# LG_G6_controller_2021-01-08.net
KiCad netlist of a schematic drawn in EasyEDA
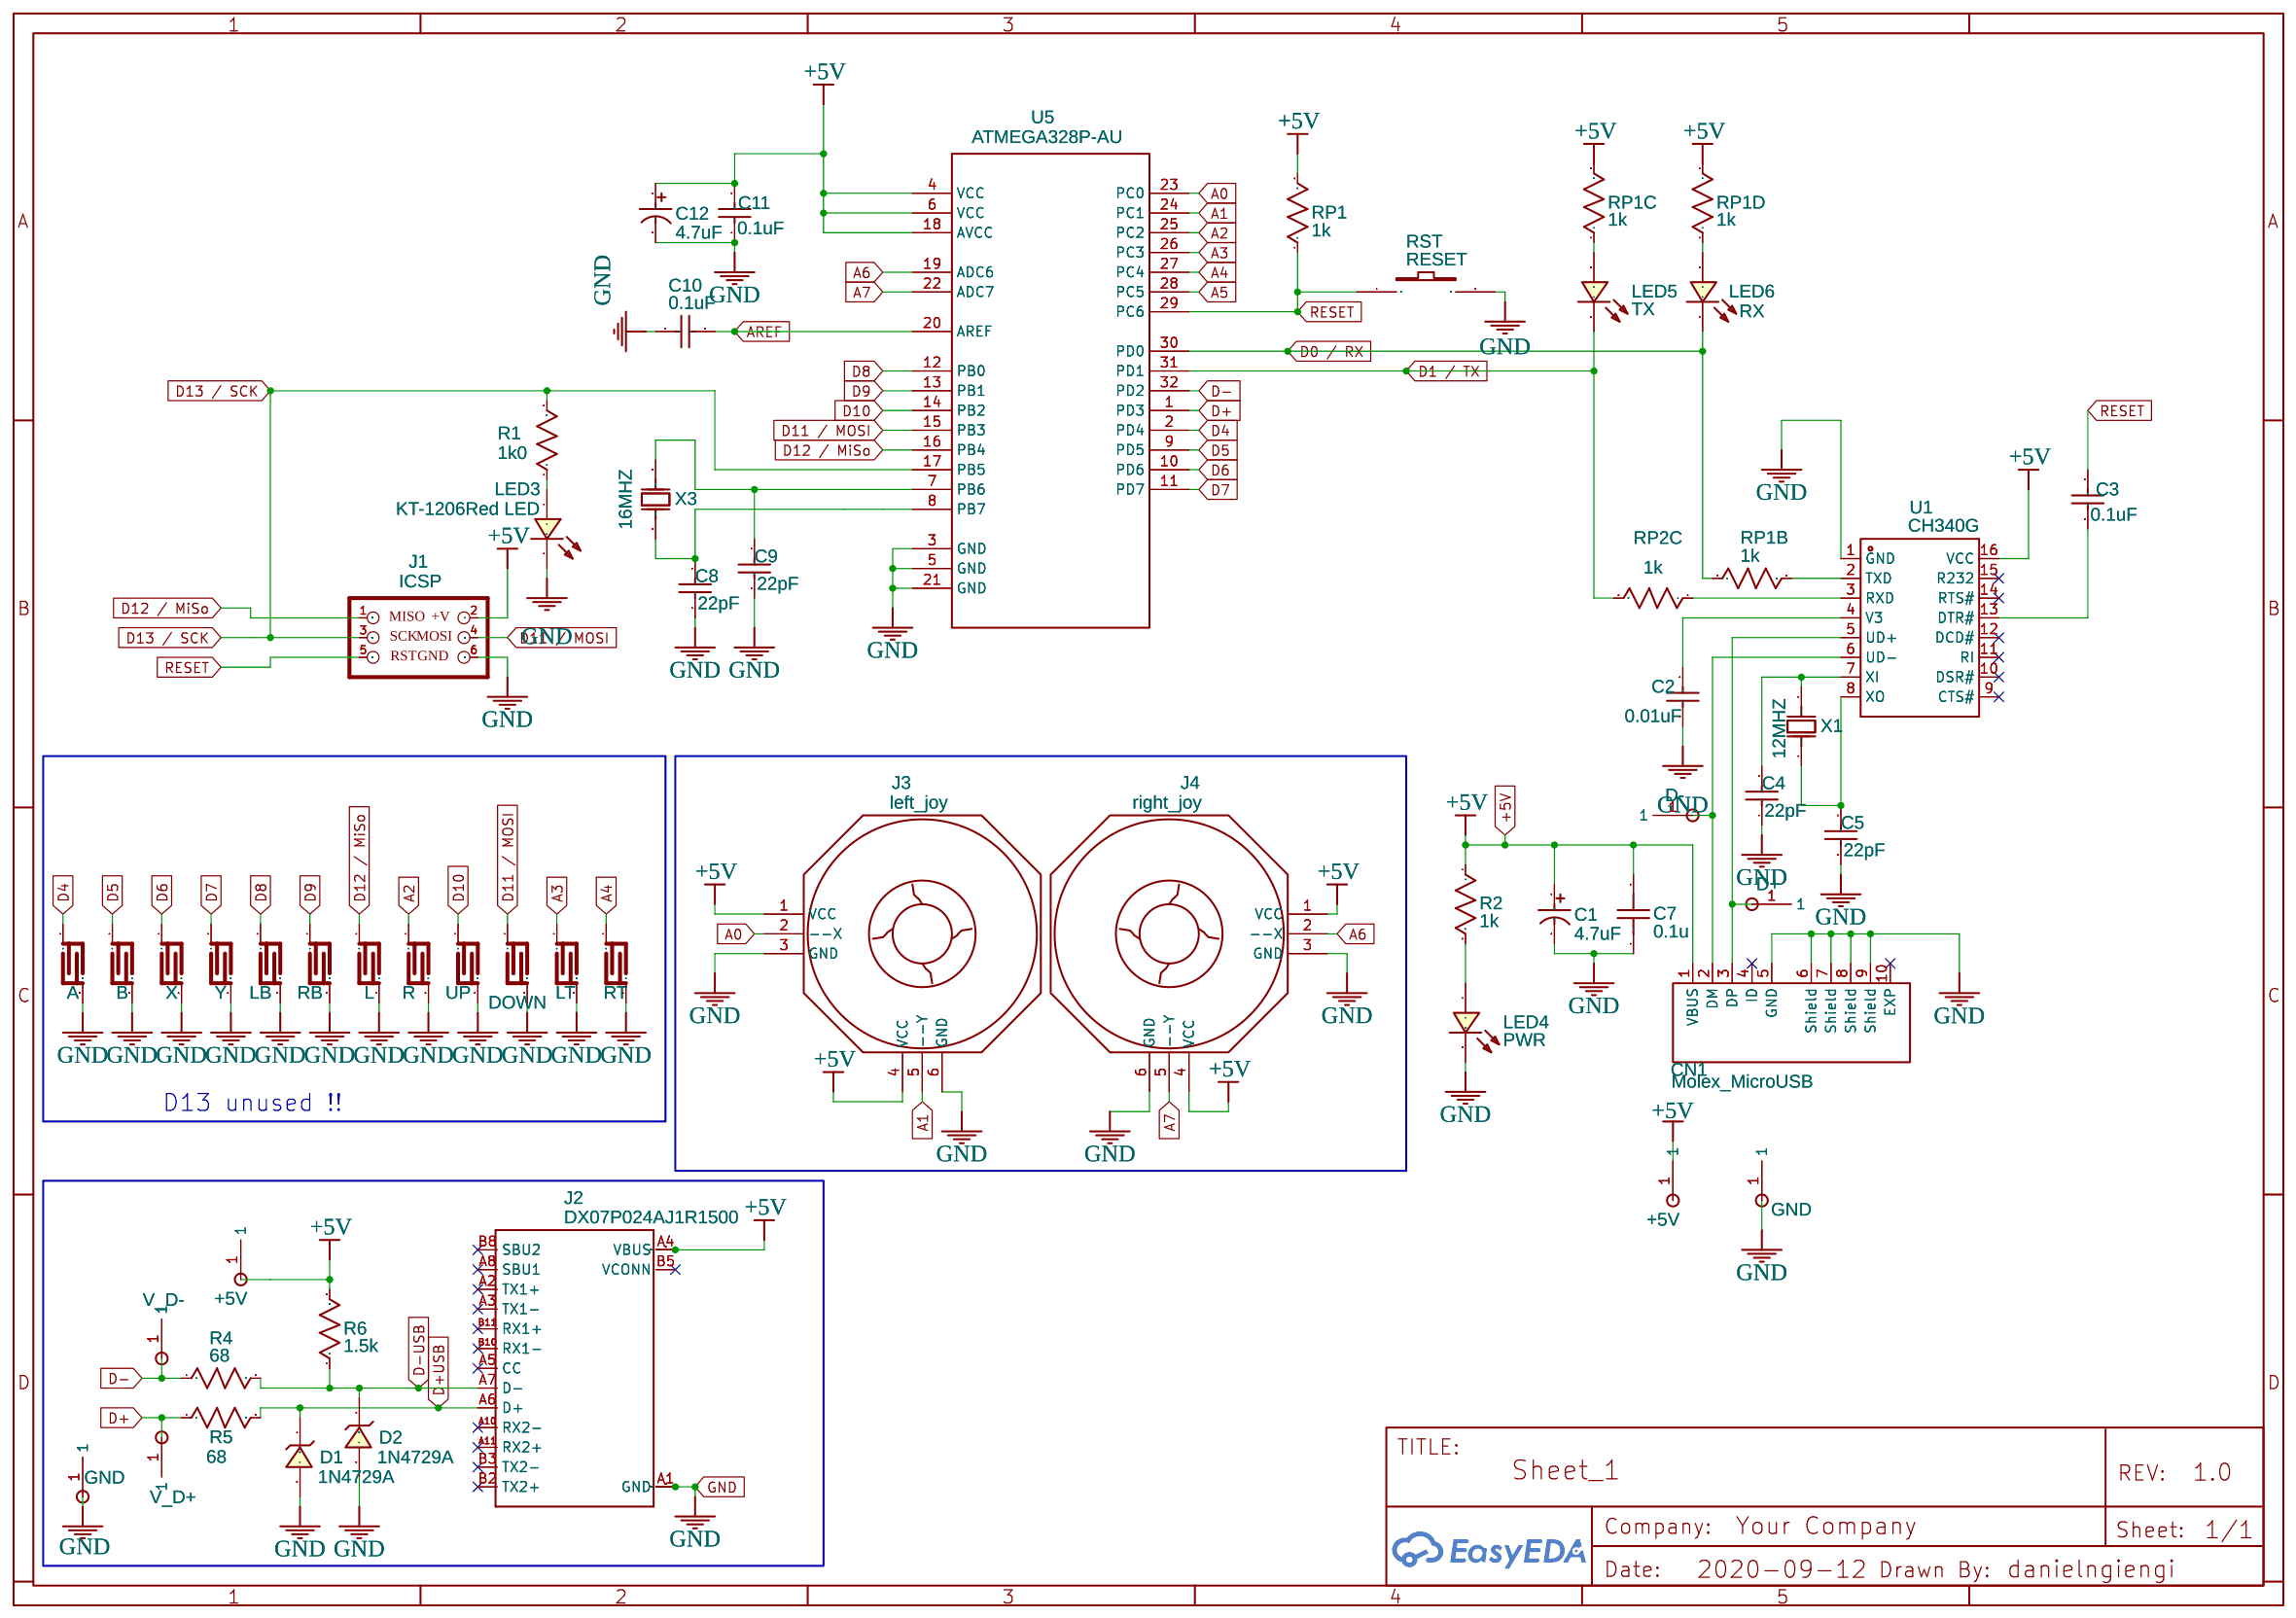
[diagram p0: schematic sheet]

(export (version "E")
  (design (tool "Eeschema 10.0.6"))
  (components
    (comp (ref "C1")
      (value "4.7uF")
      (fields
        (field (name "BOM_Manufacturer Part") "10uF 25V 4*5")
        (field (name "BOM_Supplier Part") "C43846")
      )
      (libsource (lib "") (part "10uF 25V 4*5"))
    )
    (comp (ref "C2")
      (value "0.01uF")
      (fields
        (field (name "BOM_Manufacturer Part") "C1206X224K251T 3K")
        (field (name "BOM_Supplier Part") "C106050")
      )
      (libsource (lib "") (part "C1206X224K251T 3K"))
    )
    (comp (ref "C3")
      (value "0.1uF")
      (fields
        (field (name "BOM_Manufacturer Part") "C1206X224K251T 3K")
        (field (name "BOM_Supplier Part") "C106050")
      )
      (libsource (lib "") (part "C1206X224K251T 3K"))
    )
    (comp (ref "C4")
      (value "22pF")
      (fields
        (field (name "BOM_Manufacturer Part") "C1206X224K251T 3K")
        (field (name "BOM_Supplier Part") "C106050")
      )
      (libsource (lib "") (part "C1206X224K251T 3K"))
    )
    (comp (ref "C5")
      (value "22pF")
      (fields
        (field (name "BOM_Manufacturer Part") "C1206X224K251T 3K")
        (field (name "BOM_Supplier Part") "C106050")
      )
      (libsource (lib "") (part "C1206X224K251T 3K"))
    )
    (comp (ref "C7")
      (value "0.1u")
      (fields (field (name "BOM_Manufacturer Part") "?"))
      (libsource (lib "") (part "Cap_RAD-0.1_US"))
    )
    (comp (ref "C8")
      (value "22pF")
      (fields
        (field (name "BOM_Manufacturer Part") "C1206X224K251T 3K")
        (field (name "BOM_Supplier Part") "C106050")
      )
      (libsource (lib "") (part "C1206X224K251T 3K"))
    )
    (comp (ref "C9")
      (value "22pF")
      (fields
        (field (name "BOM_Manufacturer Part") "C1206X224K251T 3K")
        (field (name "BOM_Supplier Part") "C106050")
      )
      (libsource (lib "") (part "C1206X224K251T 3K"))
    )
    (comp (ref "C10")
      (value "0.1uF")
      (fields
        (field (name "BOM_Manufacturer Part") "C1206X224K251T 3K")
        (field (name "BOM_Supplier Part") "C106050")
      )
      (libsource (lib "") (part "C1206X224K251T 3K_1"))
    )
    (comp (ref "C11")
      (value "0.1uF")
      (fields
        (field (name "BOM_Manufacturer Part") "C1206X224K251T 3K")
        (field (name "BOM_Supplier Part") "C106050")
      )
      (libsource (lib "") (part "C1206X224K251T 3K"))
    )
    (comp (ref "C12")
      (value "4.7uF")
      (fields
        (field (name "BOM_Manufacturer Part") "10uF 25V 4*5")
        (field (name "BOM_Supplier Part") "C43846")
      )
      (libsource (lib "") (part "10uF 25V 4*5"))
    )
    (comp (ref "CN1")
      (value "Molex_MicroUSB")
      (fields
        (field (name "BOM_Manufacturer Part") "0475900001")
        (field (name "BOM_Supplier Part") "WM17144CT-ND")
      )
      (libsource (lib "") (part "Molex_MicroUSB"))
    )
    (comp (ref "D1")
      (value "1N4729A")
      (fields (field (name "BOM_Supplier Part") "C2532"))
      (libsource (lib "") (part "1N4729A"))
    )
    (comp (ref "D2")
      (value "1N4729A")
      (fields (field (name "BOM_Supplier Part") "C2532"))
      (libsource (lib "") (part "1N4729A"))
    )
    (comp (ref "J1")
      (value "ICSP")
      (fields (field (name "BOM_Manufacturer Part") "?"))
      (libsource (lib "") (part "Unknown_205_-490"))
    )
    (comp (ref "J2") (value "DX07P024AJ1R1500") (libsource (lib "") (part "DX07P024AJ1R1500")))
    (comp (ref "J3") (value "left_joy") (libsource (lib "") (part "PSP-JoyStick-90")))
    (comp (ref "J4") (value "right_joy") (libsource (lib "") (part "PSP-JoyStick-90_1")))
    (comp (ref "LED3")
      (value "KT-1206Red LED")
      (fields (field (name "BOM_Supplier Part") "C49018"))
      (libsource (lib "") (part "KT-1206Red LED"))
    )
    (comp (ref "LED4")
      (value "PWR")
      (fields
        (field (name "BOM_Manufacturer Part") "KT-1206Red LED")
        (field (name "BOM_Supplier Part") "C49018")
      )
      (libsource (lib "") (part "KT-1206Red LED"))
    )
    (comp (ref "LED5")
      (value "TX")
      (fields
        (field (name "BOM_Manufacturer Part") "KT-1206Red LED")
        (field (name "BOM_Supplier Part") "C49018")
      )
      (libsource (lib "") (part "KT-1206Red LED"))
    )
    (comp (ref "LED6")
      (value "RX")
      (fields
        (field (name "BOM_Manufacturer Part") "KT-1206Red LED")
        (field (name "BOM_Supplier Part") "C49018")
      )
      (libsource (lib "") (part "KT-1206Red LED"))
    )
    (comp (ref "R1")
      (value "1k0")
      (fields (field (name "BOM_Manufacturer Part") "?"))
      (libsource (lib "") (part "Res_AXIAL-0.3(1/8W)_US_1"))
    )
    (comp (ref "R2")
      (value "1k")
      (fields (field (name "BOM_Manufacturer Part") "?"))
      (libsource (lib "") (part "Res_AXIAL-0.3(1/8W)_US_5"))
    )
    (comp (ref "R4")
      (value "68")
      (fields (field (name "BOM_Manufacturer Part") "?"))
      (libsource (lib "") (part "Res_AXIAL-0.3(1/8W)_US"))
    )
    (comp (ref "R5")
      (value "68")
      (fields (field (name "BOM_Manufacturer Part") "?"))
      (libsource (lib "") (part "Res_AXIAL-0.3(1/8W)_US"))
    )
    (comp (ref "R6")
      (value "1.5k")
      (fields (field (name "BOM_Manufacturer Part") "?"))
      (libsource (lib "") (part "Res_AXIAL-0.3(1/8W)_US_1"))
    )
    (comp (ref "RP1")
      (value "1k")
      (fields (field (name "BOM_Manufacturer Part") "?"))
      (libsource (lib "") (part "Res_AXIAL-0.3(1/8W)_US_3"))
    )
    (comp (ref "RP1B")
      (value "1k")
      (fields (field (name "BOM_Manufacturer Part") "?"))
      (libsource (lib "") (part "Res_AXIAL-0.3(1/8W)_US_7"))
    )
    (comp (ref "RP1C")
      (value "1k")
      (fields (field (name "BOM_Manufacturer Part") "?"))
      (libsource (lib "") (part "Res_AXIAL-0.3(1/8W)_US_2"))
    )
    (comp (ref "RP1D")
      (value "1k")
      (fields (field (name "BOM_Manufacturer Part") "?"))
      (libsource (lib "") (part "Res_AXIAL-0.3(1/8W)_US_4"))
    )
    (comp (ref "RP2C")
      (value "1k")
      (fields (field (name "BOM_Manufacturer Part") "?"))
      (libsource (lib "") (part "Res_AXIAL-0.3(1/8W)_US_6"))
    )
    (comp (ref "RST")
      (value "RESET")
      (fields (field (name "BOM_Manufacturer Part") "EVQ22705R") (field (name "BOM_Supplier Part") "C79156"))
      (libsource (lib "") (part "Unknown_715_-665"))
    )
    (comp (ref "S1") (value "B") (libsource (lib "") (part "CARBON-KEY-OBA")))
    (comp (ref "S3") (value "X") (libsource (lib "") (part "CARBON-KEY-OBA")))
    (comp (ref "S4") (value "Y") (libsource (lib "") (part "CARBON-KEY-OBA")))
    (comp (ref "S5") (value "A") (libsource (lib "") (part "CARBON-KEY-OBA")))
    (comp (ref "S6") (value "LB") (libsource (lib "") (part "CARBON-KEY-OBA")))
    (comp (ref "S7") (value "RB") (libsource (lib "") (part "CARBON-KEY-OBA")))
    (comp (ref "S8") (value "L") (libsource (lib "") (part "CARBON-KEY-OBA")))
    (comp (ref "S9") (value "R") (libsource (lib "") (part "CARBON-KEY-OBA")))
    (comp (ref "S10") (value "UP") (libsource (lib "") (part "CARBON-KEY-OBA")))
    (comp (ref "S11") (value "DOWN") (libsource (lib "") (part "CARBON-KEY-OBA")))
    (comp (ref "S12") (value "LT") (libsource (lib "") (part "CARBON-KEY-OBA")))
    (comp (ref "S13") (value "RT") (libsource (lib "") (part "CARBON-KEY-OBA")))
    (comp (ref "U1")
      (value "CH340G")
      (fields (field (name "BOM_Supplier Part") "C14267"))
      (libsource (lib "") (part "CH340G"))
    )
    (comp (ref "U2")
      (value "+5V")
      (fields (field (name "BOM_Manufacturer Part") "pin pad"))
      (libsource (lib "") (part "Pin"))
    )
    (comp (ref "U3")
      (value "D-")
      (fields (field (name "BOM_Manufacturer Part") "pin pad"))
      (libsource (lib "") (part "Pin_2"))
    )
    (comp (ref "U4")
      (value "D+")
      (fields (field (name "BOM_Manufacturer Part") "pin pad"))
      (libsource (lib "") (part "Pin_3"))
    )
    (comp (ref "U5")
      (value "ATMEGA328P-AU")
      (fields (field (name "BOM_Supplier Part") "C14877"))
      (libsource (lib "") (part "Unknown_525_-625"))
    )
    (comp (ref "U6")
      (value "GND")
      (fields (field (name "BOM_Manufacturer Part") "pin pad"))
      (libsource (lib "") (part "Pin"))
    )
    (comp (ref "U7")
      (value "+5V")
      (fields (field (name "BOM_Manufacturer Part") "pin pad"))
      (libsource (lib "") (part "Pin"))
    )
    (comp (ref "U8")
      (value "V_D-")
      (fields (field (name "BOM_Manufacturer Part") "pin pad"))
      (libsource (lib "") (part "Pin"))
    )
    (comp (ref "U9")
      (value "V_D+")
      (fields (field (name "BOM_Manufacturer Part") "pin pad"))
      (libsource (lib "") (part "Pin_1"))
    )
    (comp (ref "U10")
      (value "GND")
      (fields (field (name "BOM_Manufacturer Part") "pin pad"))
      (libsource (lib "") (part "Pin"))
    )
    (comp (ref "X1")
      (value "12MHZ")
      (fields
        (field (name "BOM_Manufacturer Part") "49SAC16000202060")
        (field (name "BOM_Supplier Part") "C390745")
      )
      (libsource (lib "") (part "49SAC16000202060"))
    )
    (comp (ref "X3")
      (value "16MHZ")
      (fields
        (field (name "BOM_Manufacturer Part") "49SAC16000202060")
        (field (name "BOM_Supplier Part") "C390745")
      )
      (libsource (lib "") (part "49SAC16000202060"))
    )
  )
  (nets
    (net (code "1") (name "+5V") (class "Default")
      (node (ref "C1") (pin "1") (pinfunction "1_1") (pintype "input"))
      (node (ref "C11") (pin "2") (pinfunction "2_2") (pintype "input"))
      (node (ref "C12") (pin "1") (pinfunction "1_1") (pintype "input"))
      (node (ref "C7") (pin "2") (pinfunction "2_2") (pintype "unspecified"))
      (node (ref "CN1") (pin "1") (pinfunction "VBUS_1") (pintype "unspecified"))
      (node (ref "J1") (pin "2") (pinfunction "+V_2") (pintype "unspecified"))
      (node (ref "J2") (pin "A4") (pinfunction "VBUS_A4") (pintype "bidirectional"))
      (node (ref "J2") (pin "A9") (pinfunction "VBUS_A9") (pintype "bidirectional"))
      (node (ref "J2") (pin "B4") (pinfunction "VBUS_B4") (pintype "bidirectional"))
      (node (ref "J2") (pin "B9") (pinfunction "VBUS_B9") (pintype "bidirectional"))
      (node (ref "J3") (pin "1") (pinfunction "VCC_1") (pintype "unspecified"))
      (node (ref "J3") (pin "4") (pinfunction "VCC_4") (pintype "unspecified"))
      (node (ref "J4") (pin "1") (pinfunction "VCC_1") (pintype "unspecified"))
      (node (ref "J4") (pin "4") (pinfunction "VCC_4") (pintype "unspecified"))
      (node (ref "R2") (pin "1") (pinfunction "1_1") (pintype "unspecified"))
      (node (ref "R6") (pin "2") (pinfunction "2_2") (pintype "unspecified"))
      (node (ref "RP1") (pin "2") (pinfunction "2_2") (pintype "unspecified"))
      (node (ref "RP1C") (pin "2") (pinfunction "2_2") (pintype "unspecified"))
      (node (ref "RP1D") (pin "2") (pinfunction "2_2") (pintype "unspecified"))
      (node (ref "U1") (pin "16") (pinfunction "VCC_16") (pintype "unspecified"))
      (node (ref "U2") (pin "1") (pinfunction "1_1") (pintype "unspecified"))
      (node (ref "U5") (pin "18") (pinfunction "AVCC_18") (pintype "passive"))
      (node (ref "U5") (pin "4") (pinfunction "VCC_4") (pintype "passive"))
      (node (ref "U5") (pin "6") (pinfunction "VCC_6") (pintype "passive"))
      (node (ref "U7") (pin "1") (pinfunction "1_1") (pintype "unspecified"))
    )
    (net (code "2") (name "A0") (class "Default")
      (node (ref "J3") (pin "2") (pinfunction "--X_2") (pintype "unspecified"))
      (node (ref "U5") (pin "23") (pinfunction "PC0_23") (pintype "unspecified"))
    )
    (net (code "3") (name "A1") (class "Default")
      (node (ref "J3") (pin "5") (pinfunction "--Y_5") (pintype "unspecified"))
      (node (ref "U5") (pin "24") (pinfunction "PC1_24") (pintype "unspecified"))
    )
    (net (code "4") (name "A2") (class "Default")
      (node (ref "S9") (pin "1") (pinfunction "1_1") (pintype "input"))
      (node (ref "U5") (pin "25") (pinfunction "PC2_25") (pintype "unspecified"))
    )
    (net (code "5") (name "A3") (class "Default")
      (node (ref "S12") (pin "1") (pinfunction "1_1") (pintype "input"))
      (node (ref "U5") (pin "26") (pinfunction "PC3_26") (pintype "unspecified"))
    )
    (net (code "6") (name "A4") (class "Default")
      (node (ref "S13") (pin "1") (pinfunction "1_1") (pintype "input"))
      (node (ref "U5") (pin "27") (pinfunction "PC4_27") (pintype "unspecified"))
    )
    (net (code "7") (name "A5") (class "Default")
      (node (ref "U5") (pin "28") (pinfunction "PC5_28") (pintype "unspecified"))
    )
    (net (code "8") (name "A6") (class "Default")
      (node (ref "J4") (pin "2") (pinfunction "--X_2") (pintype "unspecified"))
      (node (ref "U5") (pin "19") (pinfunction "ADC6_19") (pintype "input"))
    )
    (net (code "9") (name "A7") (class "Default")
      (node (ref "J4") (pin "5") (pinfunction "--Y_5") (pintype "unspecified"))
      (node (ref "U5") (pin "22") (pinfunction "ADC7_22") (pintype "input"))
    )
    (net (code "10") (name "AREF") (class "Default")
      (node (ref "C10") (pin "1") (pinfunction "1_1") (pintype "input"))
      (node (ref "U5") (pin "20") (pinfunction "AREF_20") (pintype "input"))
    )
    (net (code "11") (name "D+") (class "Default")
      (node (ref "R5") (pin "1") (pinfunction "1_1") (pintype "unspecified"))
      (node (ref "U5") (pin "1") (pinfunction "PD3_1") (pintype "unspecified"))
      (node (ref "U9") (pin "1") (pinfunction "1_1") (pintype "unspecified"))
    )
    (net (code "12") (name "D+USB") (class "Default")
      (node (ref "D1") (pin "1") (pinfunction "C_1") (pintype "unspecified"))
      (node (ref "J2") (pin "A6") (pinfunction "D+_A6") (pintype "bidirectional"))
      (node (ref "R5") (pin "2") (pinfunction "2_2") (pintype "unspecified"))
    )
    (net (code "13") (name "D-") (class "Default")
      (node (ref "R4") (pin "1") (pinfunction "1_1") (pintype "unspecified"))
      (node (ref "U5") (pin "32") (pinfunction "PD2_32") (pintype "unspecified"))
      (node (ref "U8") (pin "1") (pinfunction "1_1") (pintype "unspecified"))
    )
    (net (code "14") (name "D-USB") (class "Default")
      (node (ref "D2") (pin "1") (pinfunction "C_1") (pintype "unspecified"))
      (node (ref "J2") (pin "A7") (pinfunction "D-_A7") (pintype "bidirectional"))
      (node (ref "R4") (pin "2") (pinfunction "2_2") (pintype "unspecified"))
      (node (ref "R6") (pin "1") (pinfunction "1_1") (pintype "unspecified"))
    )
    (net (code "15") (name "D0 {slash} RX") (class "Default")
      (node (ref "LED6") (pin "2") (pinfunction "K_2") (pintype "unspecified"))
      (node (ref "RP1B") (pin "1") (pinfunction "1_1") (pintype "unspecified"))
      (node (ref "U5") (pin "30") (pinfunction "PD0_30") (pintype "unspecified"))
    )
    (net (code "16") (name "D1 {slash} TX") (class "Default")
      (node (ref "LED5") (pin "2") (pinfunction "K_2") (pintype "unspecified"))
      (node (ref "RP2C") (pin "2") (pinfunction "2_2") (pintype "unspecified"))
      (node (ref "U5") (pin "31") (pinfunction "PD1_31") (pintype "unspecified"))
    )
    (net (code "17") (name "D4") (class "Default")
      (node (ref "S5") (pin "1") (pinfunction "1_1") (pintype "input"))
      (node (ref "U5") (pin "2") (pinfunction "PD4_2") (pintype "unspecified"))
    )
    (net (code "18") (name "D5") (class "Default")
      (node (ref "S1") (pin "1") (pinfunction "1_1") (pintype "input"))
      (node (ref "U5") (pin "9") (pinfunction "PD5_9") (pintype "unspecified"))
    )
    (net (code "19") (name "D6") (class "Default")
      (node (ref "S3") (pin "1") (pinfunction "1_1") (pintype "input"))
      (node (ref "U5") (pin "10") (pinfunction "PD6_10") (pintype "unspecified"))
    )
    (net (code "20") (name "D7") (class "Default")
      (node (ref "S4") (pin "1") (pinfunction "1_1") (pintype "input"))
      (node (ref "U5") (pin "11") (pinfunction "PD7_11") (pintype "unspecified"))
    )
    (net (code "21") (name "D8") (class "Default")
      (node (ref "S6") (pin "1") (pinfunction "1_1") (pintype "input"))
      (node (ref "U5") (pin "12") (pinfunction "PB0_12") (pintype "unspecified"))
    )
    (net (code "22") (name "D9") (class "Default")
      (node (ref "S7") (pin "1") (pinfunction "1_1") (pintype "input"))
      (node (ref "U5") (pin "13") (pinfunction "PB1_13") (pintype "unspecified"))
    )
    (net (code "23") (name "D10") (class "Default")
      (node (ref "S10") (pin "1") (pinfunction "1_1") (pintype "input"))
      (node (ref "U5") (pin "14") (pinfunction "PB2_14") (pintype "unspecified"))
    )
    (net (code "24") (name "D11 {slash} MOSI") (class "Default")
      (node (ref "J1") (pin "4") (pinfunction "MOSI_4") (pintype "unspecified"))
      (node (ref "S11") (pin "1") (pinfunction "1_1") (pintype "input"))
      (node (ref "U5") (pin "15") (pinfunction "PB3_15") (pintype "unspecified"))
    )
    (net (code "25") (name "D12 {slash} MiSo") (class "Default")
      (node (ref "J1") (pin "1") (pinfunction "MISO_1") (pintype "unspecified"))
      (node (ref "S8") (pin "1") (pinfunction "1_1") (pintype "input"))
      (node (ref "U5") (pin "16") (pinfunction "PB4_16") (pintype "unspecified"))
    )
    (net (code "26") (name "D13 {slash} SCK") (class "Default")
      (node (ref "J1") (pin "3") (pinfunction "SCK_3") (pintype "unspecified"))
      (node (ref "R1") (pin "2") (pinfunction "2_2") (pintype "unspecified"))
      (node (ref "U5") (pin "17") (pinfunction "PB5_17") (pintype "unspecified"))
    )
    (net (code "27") (name "GND") (class "Default")
      (node (ref "C1") (pin "2") (pinfunction "2_2") (pintype "input"))
      (node (ref "C10") (pin "2") (pinfunction "2_2") (pintype "input"))
      (node (ref "C11") (pin "1") (pinfunction "1_1") (pintype "input"))
      (node (ref "C12") (pin "2") (pinfunction "2_2") (pintype "input"))
      (node (ref "C2") (pin "1") (pinfunction "1_1") (pintype "input"))
      (node (ref "C4") (pin "1") (pinfunction "1_1") (pintype "input"))
      (node (ref "C5") (pin "1") (pinfunction "1_1") (pintype "input"))
      (node (ref "C7") (pin "1") (pinfunction "1_1") (pintype "unspecified"))
      (node (ref "C8") (pin "1") (pinfunction "1_1") (pintype "input"))
      (node (ref "C9") (pin "1") (pinfunction "1_1") (pintype "input"))
      (node (ref "CN1") (pin "5") (pinfunction "GND_5") (pintype "unspecified"))
      (node (ref "CN1") (pin "6") (pinfunction "Shield_6") (pintype "input"))
      (node (ref "CN1") (pin "7") (pinfunction "Shield_7") (pintype "input"))
      (node (ref "CN1") (pin "8") (pinfunction "Shield_8") (pintype "input"))
      (node (ref "CN1") (pin "9") (pinfunction "Shield_9") (pintype "input"))
      (node (ref "D1") (pin "2") (pinfunction "A_2") (pintype "unspecified"))
      (node (ref "D2") (pin "2") (pinfunction "A_2") (pintype "unspecified"))
      (node (ref "J1") (pin "6") (pinfunction "GND_6") (pintype "unspecified"))
      (node (ref "J2") (pin "A1") (pinfunction "GND_A1") (pintype "bidirectional"))
      (node (ref "J2") (pin "A12") (pinfunction "GND_A12") (pintype "bidirectional"))
      (node (ref "J2") (pin "B1") (pinfunction "GND_B1") (pintype "bidirectional"))
      (node (ref "J2") (pin "B12") (pinfunction "GND_B12") (pintype "bidirectional"))
      (node (ref "J3") (pin "3") (pinfunction "GND_3") (pintype "unspecified"))
      (node (ref "J3") (pin "6") (pinfunction "GND_6") (pintype "unspecified"))
      (node (ref "J4") (pin "3") (pinfunction "GND_3") (pintype "unspecified"))
      (node (ref "J4") (pin "6") (pinfunction "GND_6") (pintype "unspecified"))
      (node (ref "LED3") (pin "2") (pinfunction "K_2") (pintype "unspecified"))
      (node (ref "LED4") (pin "2") (pinfunction "K_2") (pintype "unspecified"))
      (node (ref "RST") (pin "2") (pinfunction "2_2") (pintype "input"))
      (node (ref "S1") (pin "2") (pinfunction "2_2") (pintype "input"))
      (node (ref "S10") (pin "2") (pinfunction "2_2") (pintype "input"))
      (node (ref "S11") (pin "2") (pinfunction "2_2") (pintype "input"))
      (node (ref "S12") (pin "2") (pinfunction "2_2") (pintype "input"))
      (node (ref "S13") (pin "2") (pinfunction "2_2") (pintype "input"))
      (node (ref "S3") (pin "2") (pinfunction "2_2") (pintype "input"))
      (node (ref "S4") (pin "2") (pinfunction "2_2") (pintype "input"))
      (node (ref "S5") (pin "2") (pinfunction "2_2") (pintype "input"))
      (node (ref "S6") (pin "2") (pinfunction "2_2") (pintype "input"))
      (node (ref "S7") (pin "2") (pinfunction "2_2") (pintype "input"))
      (node (ref "S8") (pin "2") (pinfunction "2_2") (pintype "input"))
      (node (ref "S9") (pin "2") (pinfunction "2_2") (pintype "input"))
      (node (ref "U1") (pin "1") (pinfunction "GND_1") (pintype "unspecified"))
      (node (ref "U10") (pin "1") (pinfunction "1_1") (pintype "unspecified"))
      (node (ref "U5") (pin "21") (pinfunction "GND_21") (pintype "unspecified"))
      (node (ref "U5") (pin "3") (pinfunction "GND_3") (pintype "unspecified"))
      (node (ref "U5") (pin "5") (pinfunction "GND_5") (pintype "unspecified"))
      (node (ref "U6") (pin "1") (pinfunction "1_1") (pintype "unspecified"))
    )
    (net (code "28") (name "Net-(CN1-DM)") (class "Default")
      (node (ref "CN1") (pin "2") (pinfunction "DM_2") (pintype "unspecified"))
      (node (ref "U1") (pin "6") (pinfunction "UD-_6") (pintype "unspecified"))
      (node (ref "U3") (pin "1") (pinfunction "1_1") (pintype "unspecified"))
    )
    (net (code "29") (name "Net-(CN1-DP)") (class "Default")
      (node (ref "CN1") (pin "3") (pinfunction "DP_3") (pintype "unspecified"))
      (node (ref "U1") (pin "5") (pinfunction "UD+_5") (pintype "unspecified"))
      (node (ref "U4") (pin "1") (pinfunction "1_1") (pintype "unspecified"))
    )
    (net (code "30") (name "Net-(LED3-A)") (class "Default")
      (node (ref "LED3") (pin "1") (pinfunction "A_1") (pintype "unspecified"))
      (node (ref "R1") (pin "1") (pinfunction "1_1") (pintype "unspecified"))
    )
    (net (code "31") (name "Net-(LED4-A)") (class "Default")
      (node (ref "LED4") (pin "1") (pinfunction "A_1") (pintype "unspecified"))
      (node (ref "R2") (pin "2") (pinfunction "2_2") (pintype "unspecified"))
    )
    (net (code "32") (name "Net-(LED5-A)") (class "Default")
      (node (ref "LED5") (pin "1") (pinfunction "A_1") (pintype "unspecified"))
      (node (ref "RP1C") (pin "1") (pinfunction "1_1") (pintype "unspecified"))
    )
    (net (code "33") (name "Net-(LED6-A)") (class "Default")
      (node (ref "LED6") (pin "1") (pinfunction "A_1") (pintype "unspecified"))
      (node (ref "RP1D") (pin "1") (pinfunction "1_1") (pintype "unspecified"))
    )
    (net (code "34") (name "Net-(U1-DTR#)") (class "Default")
      (node (ref "C3") (pin "1") (pinfunction "1_1") (pintype "input"))
      (node (ref "U1") (pin "13") (pinfunction "DTR#_13") (pintype "unspecified"))
    )
    (net (code "35") (name "Net-(U1-RXD)") (class "Default")
      (node (ref "RP2C") (pin "1") (pinfunction "1_1") (pintype "unspecified"))
      (node (ref "U1") (pin "3") (pinfunction "RXD_3") (pintype "unspecified"))
    )
    (net (code "36") (name "Net-(U1-TXD)") (class "Default")
      (node (ref "RP1B") (pin "2") (pinfunction "2_2") (pintype "unspecified"))
      (node (ref "U1") (pin "2") (pinfunction "TXD_2") (pintype "unspecified"))
    )
    (net (code "37") (name "Net-(U1-V3)") (class "Default")
      (node (ref "C2") (pin "2") (pinfunction "2_2") (pintype "input"))
      (node (ref "U1") (pin "4") (pinfunction "V3_4") (pintype "unspecified"))
    )
    (net (code "38") (name "Net-(U1-XI)") (class "Default")
      (node (ref "C4") (pin "2") (pinfunction "2_2") (pintype "input"))
      (node (ref "U1") (pin "7") (pinfunction "XI_7") (pintype "unspecified"))
      (node (ref "X1") (pin "2") (pinfunction "OSC2_2") (pintype "input"))
    )
    (net (code "39") (name "Net-(U1-XO)") (class "Default")
      (node (ref "C5") (pin "2") (pinfunction "2_2") (pintype "input"))
      (node (ref "U1") (pin "8") (pinfunction "XO_8") (pintype "unspecified"))
      (node (ref "X1") (pin "1") (pinfunction "OSC1_1") (pintype "input"))
    )
    (net (code "40") (name "Net-(U5-PB6)") (class "Default")
      (node (ref "C9") (pin "2") (pinfunction "2_2") (pintype "input"))
      (node (ref "U5") (pin "7") (pinfunction "PB6_7") (pintype "unspecified"))
      (node (ref "X3") (pin "2") (pinfunction "OSC2_2") (pintype "input"))
    )
    (net (code "41") (name "Net-(U5-PB7)") (class "Default")
      (node (ref "C8") (pin "2") (pinfunction "2_2") (pintype "input"))
      (node (ref "U5") (pin "8") (pinfunction "PB7_8") (pintype "unspecified"))
      (node (ref "X3") (pin "1") (pinfunction "OSC1_1") (pintype "input"))
    )
    (net (code "42") (name "RESET") (class "Default")
      (node (ref "C3") (pin "2") (pinfunction "2_2") (pintype "input"))
      (node (ref "J1") (pin "5") (pinfunction "RST_5") (pintype "unspecified"))
      (node (ref "RP1") (pin "1") (pinfunction "1_1") (pintype "unspecified"))
      (node (ref "RST") (pin "1") (pinfunction "1_1") (pintype "input"))
      (node (ref "U5") (pin "29") (pinfunction "PC6_29") (pintype "unspecified"))
    )
    (net (code "43") (name "unconnected-(CN1-EXP-Pad10)") (class "Default")
      (node (ref "CN1") (pin "10") (pinfunction "EXP_10") (pintype "input+no_connect"))
    )
    (net (code "44") (name "unconnected-(CN1-ID-Pad4)") (class "Default")
      (node (ref "CN1") (pin "4") (pinfunction "ID_4") (pintype "unspecified+no_connect"))
    )
    (net (code "45") (name "unconnected-(J2-CC-PadA5)") (class "Default")
      (node (ref "J2") (pin "A5") (pinfunction "CC_A5") (pintype "bidirectional+no_connect"))
    )
    (net (code "46") (name "unconnected-(J2-RX1+-PadB11)") (class "Default")
      (node (ref "J2") (pin "B11") (pinfunction "RX1+_B11") (pintype "bidirectional+no_connect"))
    )
    (net (code "47") (name "unconnected-(J2-RX1--PadB10)") (class "Default")
      (node (ref "J2") (pin "B10") (pinfunction "RX1-_B10") (pintype "bidirectional+no_connect"))
    )
    (net (code "48") (name "unconnected-(J2-RX2+-PadA11)") (class "Default")
      (node (ref "J2") (pin "A11") (pinfunction "RX2+_A11") (pintype "bidirectional+no_connect"))
    )
    (net (code "49") (name "unconnected-(J2-RX2--PadA10)") (class "Default")
      (node (ref "J2") (pin "A10") (pinfunction "RX2-_A10") (pintype "bidirectional+no_connect"))
    )
    (net (code "50") (name "unconnected-(J2-SBU1-PadA8)") (class "Default")
      (node (ref "J2") (pin "A8") (pinfunction "SBU1_A8") (pintype "bidirectional+no_connect"))
    )
    (net (code "51") (name "unconnected-(J2-SBU2-PadB8)") (class "Default")
      (node (ref "J2") (pin "B8") (pinfunction "SBU2_B8") (pintype "bidirectional+no_connect"))
    )
    (net (code "52") (name "unconnected-(J2-TX1+-PadA2)") (class "Default")
      (node (ref "J2") (pin "A2") (pinfunction "TX1+_A2") (pintype "bidirectional+no_connect"))
    )
    (net (code "53") (name "unconnected-(J2-TX1--PadA3)") (class "Default")
      (node (ref "J2") (pin "A3") (pinfunction "TX1-_A3") (pintype "bidirectional+no_connect"))
    )
    (net (code "54") (name "unconnected-(J2-TX2+-PadB2)") (class "Default")
      (node (ref "J2") (pin "B2") (pinfunction "TX2+_B2") (pintype "bidirectional+no_connect"))
    )
    (net (code "55") (name "unconnected-(J2-TX2--PadB3)") (class "Default")
      (node (ref "J2") (pin "B3") (pinfunction "TX2-_B3") (pintype "bidirectional+no_connect"))
    )
    (net (code "56") (name "unconnected-(J2-VCONN-PadB5)") (class "Default")
      (node (ref "J2") (pin "B5") (pinfunction "VCONN_B5") (pintype "bidirectional+no_connect"))
    )
    (net (code "57") (name "unconnected-(U1-CTS#-Pad9)") (class "Default")
      (node (ref "U1") (pin "9") (pinfunction "CTS#_9") (pintype "unspecified+no_connect"))
    )
    (net (code "58") (name "unconnected-(U1-DCD#-Pad12)") (class "Default")
      (node (ref "U1") (pin "12") (pinfunction "DCD#_12") (pintype "unspecified+no_connect"))
    )
    (net (code "59") (name "unconnected-(U1-DSR#-Pad10)") (class "Default")
      (node (ref "U1") (pin "10") (pinfunction "DSR#_10") (pintype "unspecified+no_connect"))
    )
    (net (code "60") (name "unconnected-(U1-R232-Pad15)") (class "Default")
      (node (ref "U1") (pin "15") (pinfunction "R232_15") (pintype "unspecified+no_connect"))
    )
    (net (code "61") (name "unconnected-(U1-RI-Pad11)") (class "Default")
      (node (ref "U1") (pin "11") (pinfunction "RI_11") (pintype "unspecified+no_connect"))
    )
    (net (code "62") (name "unconnected-(U1-RTS#-Pad14)") (class "Default")
      (node (ref "U1") (pin "14") (pinfunction "RTS#_14") (pintype "unspecified+no_connect"))
    )
  )
)
